# sensbaseGLCD.net
KiCad netlist of a schematic drawn in EAGLE
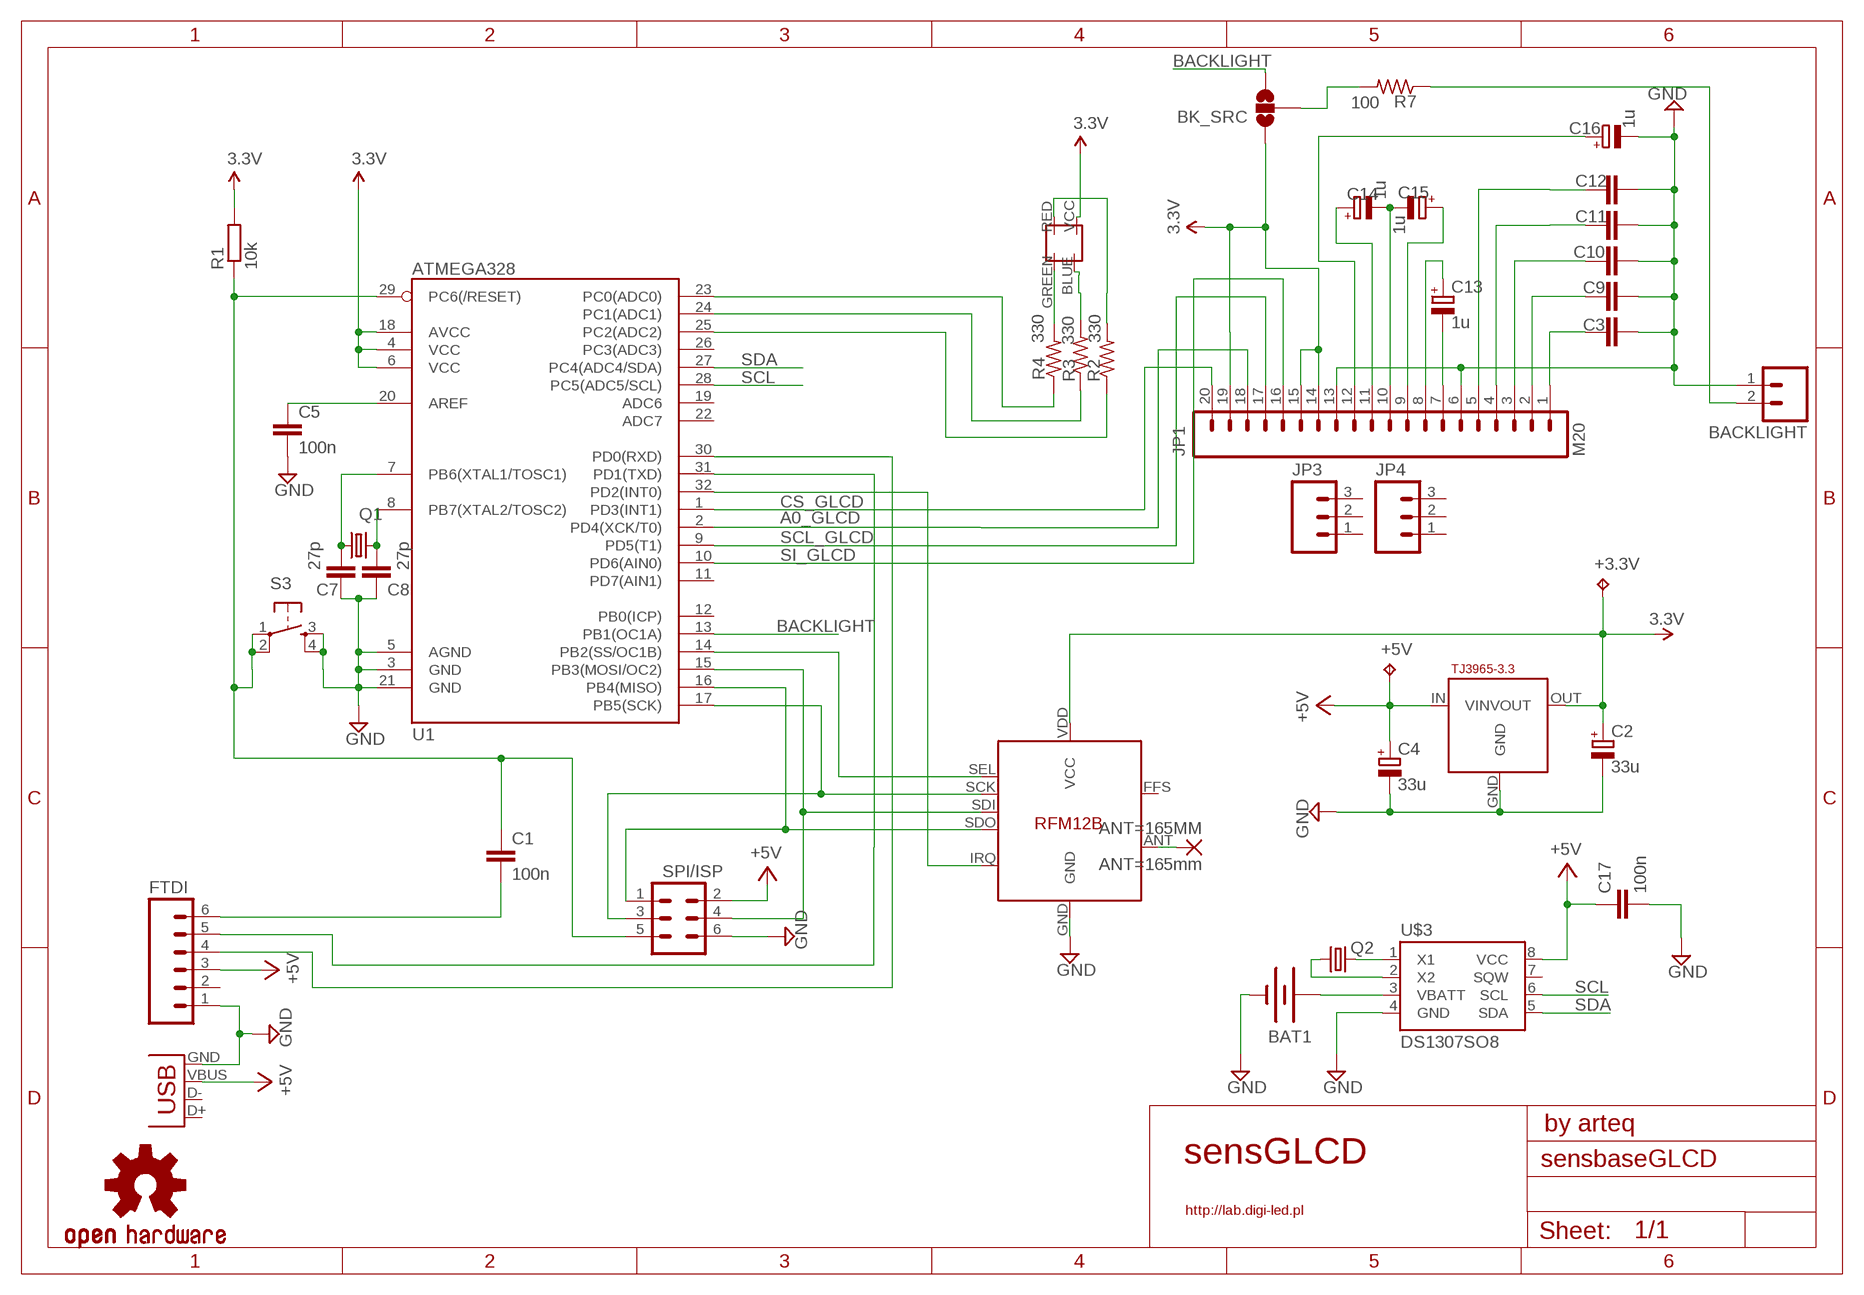
[diagram p0: schematic, sheet 1]

(export (version "E")
  (design (tool "Eeschema 10.0.6"))
  (components
    (comp (ref "+3.3V")
      (value "TPB1,27")
      (footprint "eagle-import:B1,27")
      (libsource (lib "eagle-import") (part "TPB1,27"))
    )
    (comp (ref "+5V")
      (value "TPB1,27")
      (footprint "eagle-import:B1,27")
      (libsource (lib "eagle-import") (part "TPB1,27"))
    )
    (comp (ref "3.3")
      (value "TJ3965-3.3")
      (footprint "eagle-import:SOT223")
      (libsource (lib "eagle-import") (part "TJ3965-3.3"))
    )
    (comp (ref "ANT=165MM")
      (value "ANT=165mm")
      (footprint "eagle-import:2,15_1,0")
      (libsource (lib "eagle-import") (part "2,15/1,0"))
    )
    (comp (ref "BACKLIGHT")
      (value "M02PTH")
      (footprint "eagle-import:1X02")
      (libsource (lib "eagle-import") (part "M02PTH"))
    )
    (comp (ref "BAT1")
      (value "BATTERY20PTH")
      (footprint "eagle-import:BATTCOM_20MM_PTH")
      (libsource (lib "eagle-import") (part "BATTERY20PTH"))
    )
    (comp (ref "BK_SRC")
      (value "SOLDERJUMPER_2WAYT")
      (footprint "eagle-import:SJ_2")
      (libsource (lib "eagle-import") (part "SOLDERJUMPER_2WAYT"))
    )
    (comp (ref "C1")
      (value "100n")
      (footprint "eagle-import:C0805")
      (libsource (lib "eagle-import") (part "C-EUC0805"))
    )
    (comp (ref "C2")
      (value "33u")
      (footprint "eagle-import:SMC_B")
      (libsource (lib "eagle-import") (part "CPOL-EUSMCB"))
    )
    (comp (ref "C3")
      (value "1u")
      (footprint "eagle-import:C0805")
      (libsource (lib "eagle-import") (part "C-EUC0805"))
    )
    (comp (ref "C4")
      (value "33u")
      (footprint "eagle-import:SMC_B")
      (libsource (lib "eagle-import") (part "CPOL-EUSMCB"))
    )
    (comp (ref "C5")
      (value "100n")
      (footprint "eagle-import:C0805")
      (libsource (lib "eagle-import") (part "C-EUC0805"))
    )
    (comp (ref "C7")
      (value "27p")
      (footprint "eagle-import:C0805")
      (libsource (lib "eagle-import") (part "C-EUC0805"))
    )
    (comp (ref "C8")
      (value "27p")
      (footprint "eagle-import:C0805")
      (libsource (lib "eagle-import") (part "C-EUC0805"))
    )
    (comp (ref "C9")
      (value "1u")
      (footprint "eagle-import:C0805")
      (libsource (lib "eagle-import") (part "C-EUC0805"))
    )
    (comp (ref "C10")
      (value "1u")
      (footprint "eagle-import:C0805")
      (libsource (lib "eagle-import") (part "C-EUC0805"))
    )
    (comp (ref "C11")
      (value "1u")
      (footprint "eagle-import:C0805")
      (libsource (lib "eagle-import") (part "C-EUC0805"))
    )
    (comp (ref "C12")
      (value "1u")
      (footprint "eagle-import:C0805")
      (libsource (lib "eagle-import") (part "C-EUC0805"))
    )
    (comp (ref "C13")
      (value "1u")
      (footprint "eagle-import:A_3216-18R")
      (libsource (lib "eagle-import") (part "CPOL-EUA/3216-18R"))
    )
    (comp (ref "C14")
      (value "1u")
      (footprint "eagle-import:A_3216-18R")
      (libsource (lib "eagle-import") (part "CPOL-EUA/3216-18R"))
    )
    (comp (ref "C15")
      (value "1u")
      (footprint "eagle-import:A_3216-18R")
      (libsource (lib "eagle-import") (part "CPOL-EUA/3216-18R"))
    )
    (comp (ref "C16")
      (value "1u")
      (footprint "eagle-import:A_3216-18R")
      (libsource (lib "eagle-import") (part "CPOL-EUA/3216-18R"))
    )
    (comp (ref "C17")
      (value "100n")
      (footprint "eagle-import:C0805")
      (libsource (lib "eagle-import") (part "C-EUC0805"))
    )
    (comp (ref "FTDI")
      (value "M06SIP")
      (footprint "eagle-import:1X06")
      (libsource (lib "eagle-import") (part "M06SIP"))
    )
    (comp (ref "JP1")
      (value "M20")
      (footprint "eagle-import:1X20")
      (libsource (lib "eagle-import") (part "M20"))
    )
    (comp (ref "JP3")
      (value "M03PTH")
      (footprint "eagle-import:1X03")
      (libsource (lib "eagle-import") (part "M03PTH"))
    )
    (comp (ref "JP4")
      (value "M03PTH")
      (footprint "eagle-import:1X03")
      (libsource (lib "eagle-import") (part "M03PTH"))
    )
    (comp (ref "Q1")
      (value "CRYSTALHC49UP")
      (footprint "eagle-import:HC49UP")
      (libsource (lib "eagle-import") (part "CRYSTALHC49UP"))
    )
    (comp (ref "Q2")
      (value "CRYSTALTC26H")
      (footprint "eagle-import:TC26H")
      (libsource (lib "eagle-import") (part "CRYSTALTC26H"))
    )
    (comp (ref "R1")
      (value "10k")
      (footprint "eagle-import:R0805")
      (libsource (lib "eagle-import") (part "R-EU_R0805"))
    )
    (comp (ref "R2")
      (value "330")
      (footprint "eagle-import:R0805")
      (libsource (lib "eagle-import") (part "R-US_R0805"))
    )
    (comp (ref "R3")
      (value "330")
      (footprint "eagle-import:R0805")
      (libsource (lib "eagle-import") (part "R-US_R0805"))
    )
    (comp (ref "R4")
      (value "330")
      (footprint "eagle-import:R0805")
      (libsource (lib "eagle-import") (part "R-US_R0805"))
    )
    (comp (ref "R7")
      (value "100")
      (footprint "eagle-import:R0805")
      (libsource (lib "eagle-import") (part "R-US_R0805"))
    )
    (comp (ref "RF433")
      (value "RFM12B")
      (footprint "eagle-import:RFM12B")
      (libsource (lib "eagle-import") (part "RFM12B"))
    )
    (comp (ref "S3")
      (value "TAC_SWITCHSMD")
      (footprint "eagle-import:TACTILE_SWITCH_SMD")
      (libsource (lib "eagle-import") (part "TAC_SWITCHSMD"))
    )
    (comp (ref "SV7")
      (value "SPI/ISP")
      (footprint "eagle-import:MA03-2")
      (libsource (lib "eagle-import") (part "MA03-2"))
    )
    (comp (ref "U$2")
      (value "OSHW-LOGOL")
      (footprint "eagle-import:OSHW-LOGO-L")
      (libsource (lib "eagle-import") (part "OSHW-LOGOL"))
    )
    (comp (ref "U$3")
      (value "DS1307SO8")
      (footprint "eagle-import:SO08")
      (libsource (lib "eagle-import") (part "DS1307SO8"))
    )
    (comp (ref "U$4")
      (value "RGB1206")
      (footprint "eagle-import:RGB1206")
      (libsource (lib "eagle-import") (part "RGB1206"))
    )
    (comp (ref "U1")
      (value "ATMEGA328")
      (footprint "eagle-import:TQFP32-08")
      (libsource (lib "eagle-import") (part "ATMEGA168"))
    )
    (comp (ref "X1")
      (value "USBSMD")
      (footprint "eagle-import:USB-MINIB")
      (libsource (lib "eagle-import") (part "USBSMD"))
    )
  )
  (nets
    (net (code "1") (name "+5V") (class "Default")
      (node (ref "+5V") (pin "TP") (pinfunction "TP_TP") (pintype "input"))
      (node (ref "3.3") (pin "IN") (pinfunction "VIN_IN") (pintype "input"))
      (node (ref "C17") (pin "1") (pinfunction "1_1") (pintype "passive"))
      (node (ref "C4") (pin "+") (pinfunction "+_+") (pintype "passive"))
      (node (ref "FTDI") (pin "3") (pinfunction "3_3") (pintype "passive"))
      (node (ref "SV7") (pin "2") (pinfunction "2_2") (pintype "passive"))
      (node (ref "U$3") (pin "8") (pinfunction "VCC_8") (pintype "bidirectional"))
      (node (ref "X1") (pin "VBUS") (pinfunction "VBUS_VBUS") (pintype "bidirectional"))
    )
    (net (code "2") (name "/A0_GLCD") (class "Default")
      (node (ref "JP1") (pin "18") (pinfunction "18_18") (pintype "passive"))
      (node (ref "U1") (pin "2") (pinfunction "PD4(XCK/T0)_2") (pintype "bidirectional"))
    )
    (net (code "3") (name "/BACKLIGHT") (class "Default")
      (node (ref "BK_SRC") (pin "3") (pinfunction "3_3") (pintype "passive"))
      (node (ref "U1") (pin "13") (pinfunction "PB1(OC1A)_13") (pintype "bidirectional"))
    )
    (net (code "4") (name "/CS_GLCD") (class "Default")
      (node (ref "JP1") (pin "20") (pinfunction "20_20") (pintype "passive"))
      (node (ref "U1") (pin "1") (pinfunction "PD3(INT1)_1") (pintype "bidirectional"))
    )
    (net (code "5") (name "/SCL") (class "Default")
      (node (ref "U$3") (pin "6") (pinfunction "SCL_6") (pintype "bidirectional"))
      (node (ref "U1") (pin "28") (pinfunction "PC5(ADC5/SCL)_28") (pintype "bidirectional"))
    )
    (net (code "6") (name "/SCL_GLCD") (class "Default")
      (node (ref "JP1") (pin "17") (pinfunction "17_17") (pintype "passive"))
      (node (ref "U1") (pin "9") (pinfunction "PD5(T1)_9") (pintype "bidirectional"))
    )
    (net (code "7") (name "/SDA") (class "Default")
      (node (ref "U$3") (pin "5") (pinfunction "SDA_5") (pintype "bidirectional"))
      (node (ref "U1") (pin "27") (pinfunction "PC4(ADC4/SDA)_27") (pintype "bidirectional"))
    )
    (net (code "8") (name "/SI_GLCD") (class "Default")
      (node (ref "JP1") (pin "16") (pinfunction "16_16") (pintype "passive"))
      (node (ref "U1") (pin "10") (pinfunction "PD6(AIN0)_10") (pintype "bidirectional"))
    )
    (net (code "9") (name "3.3V") (class "Default")
      (node (ref "+3.3V") (pin "TP") (pinfunction "TP_TP") (pintype "input"))
      (node (ref "3.3") (pin "OUT") (pinfunction "VOUT_OUT") (pintype "output"))
      (node (ref "BK_SRC") (pin "1") (pinfunction "1_1") (pintype "passive"))
      (node (ref "C2") (pin "+") (pinfunction "+_+") (pintype "passive"))
      (node (ref "JP1") (pin "14") (pinfunction "14_14") (pintype "passive"))
      (node (ref "JP1") (pin "15") (pinfunction "15_15") (pintype "passive"))
      (node (ref "JP1") (pin "19") (pinfunction "19_19") (pintype "passive"))
      (node (ref "R1") (pin "2") (pinfunction "2_2") (pintype "passive"))
      (node (ref "RF433") (pin "VDD") (pinfunction "VCC_VDD") (pintype "power_in"))
      (node (ref "U$4") (pin "VCC") (pinfunction "VCC_VCC") (pintype "bidirectional"))
      (node (ref "U1") (pin "18") (pinfunction "AVCC_18") (pintype "bidirectional"))
      (node (ref "U1") (pin "4") (pinfunction "VCC_4") (pintype "bidirectional"))
      (node (ref "U1") (pin "6") (pinfunction "VCC_6") (pintype "bidirectional"))
    )
    (net (code "10") (name "GND") (class "Default")
      (node (ref "3.3") (pin "GND") (pinfunction "GND_GND") (pintype "power_in"))
      (node (ref "BACKLIGHT") (pin "1") (pinfunction "1_1") (pintype "passive"))
      (node (ref "BAT1") (pin "2") (pinfunction "-_2") (pintype "power_in"))
      (node (ref "C10") (pin "2") (pinfunction "2_2") (pintype "passive"))
      (node (ref "C11") (pin "2") (pinfunction "2_2") (pintype "passive"))
      (node (ref "C12") (pin "2") (pinfunction "2_2") (pintype "passive"))
      (node (ref "C16") (pin "-") (pinfunction "-_-") (pintype "passive"))
      (node (ref "C17") (pin "2") (pinfunction "2_2") (pintype "passive"))
      (node (ref "C2") (pin "-") (pinfunction "-_-") (pintype "passive"))
      (node (ref "C3") (pin "2") (pinfunction "2_2") (pintype "passive"))
      (node (ref "C4") (pin "-") (pinfunction "-_-") (pintype "passive"))
      (node (ref "C5") (pin "2") (pinfunction "2_2") (pintype "passive"))
      (node (ref "C7") (pin "2") (pinfunction "2_2") (pintype "passive"))
      (node (ref "C8") (pin "2") (pinfunction "2_2") (pintype "passive"))
      (node (ref "C9") (pin "2") (pinfunction "2_2") (pintype "passive"))
      (node (ref "FTDI") (pin "1") (pinfunction "1_1") (pintype "passive"))
      (node (ref "JP1") (pin "13") (pinfunction "13_13") (pintype "passive"))
      (node (ref "JP1") (pin "6") (pinfunction "6_6") (pintype "passive"))
      (node (ref "RF433") (pin "GND") (pinfunction "GND_GND") (pintype "power_in"))
      (node (ref "S3") (pin "3") (pinfunction "3_3") (pintype "passive"))
      (node (ref "S3") (pin "4") (pinfunction "4_4") (pintype "passive"))
      (node (ref "SV7") (pin "6") (pinfunction "6_6") (pintype "passive"))
      (node (ref "U$3") (pin "4") (pinfunction "GND_4") (pintype "bidirectional"))
      (node (ref "U1") (pin "21") (pinfunction "GND_21") (pintype "bidirectional"))
      (node (ref "U1") (pin "3") (pinfunction "GND_3") (pintype "bidirectional"))
      (node (ref "U1") (pin "5") (pinfunction "AGND_5") (pintype "bidirectional"))
      (node (ref "X1") (pin "GND") (pinfunction "GND_GND") (pintype "bidirectional"))
    )
    (net (code "11") (name "Net-(ANT=165MM-P)") (class "Default")
      (node (ref "ANT=165MM") (pin "1") (pinfunction "P_1") (pintype "passive"))
      (node (ref "RF433") (pin "ANT") (pinfunction "ANT_ANT") (pintype "passive"))
    )
    (net (code "12") (name "Net-(BACKLIGHT-Pad2)") (class "Default")
      (node (ref "BACKLIGHT") (pin "2") (pinfunction "2_2") (pintype "passive"))
      (node (ref "R7") (pin "1") (pinfunction "1_1") (pintype "passive"))
    )
    (net (code "13") (name "Net-(BAT1-+)") (class "Default")
      (node (ref "BAT1") (pin "1") (pinfunction "+_1") (pintype "power_in"))
      (node (ref "U$3") (pin "3") (pinfunction "VBATT_3") (pintype "bidirectional"))
    )
    (net (code "14") (name "Net-(BK_SRC-Pad2)") (class "Default")
      (node (ref "BK_SRC") (pin "2") (pinfunction "2_2") (pintype "passive"))
      (node (ref "R7") (pin "2") (pinfunction "2_2") (pintype "passive"))
    )
    (net (code "15") (name "Net-(C1-Pad2)") (class "Default")
      (node (ref "C1") (pin "2") (pinfunction "2_2") (pintype "passive"))
      (node (ref "FTDI") (pin "6") (pinfunction "6_6") (pintype "passive"))
    )
    (net (code "16") (name "Net-(C3-Pad1)") (class "Default")
      (node (ref "C3") (pin "1") (pinfunction "1_1") (pintype "passive"))
      (node (ref "JP1") (pin "1") (pinfunction "1_1") (pintype "passive"))
    )
    (net (code "17") (name "Net-(C9-Pad1)") (class "Default")
      (node (ref "C9") (pin "1") (pinfunction "1_1") (pintype "passive"))
      (node (ref "JP1") (pin "2") (pinfunction "2_2") (pintype "passive"))
    )
    (net (code "18") (name "Net-(C10-Pad1)") (class "Default")
      (node (ref "C10") (pin "1") (pinfunction "1_1") (pintype "passive"))
      (node (ref "JP1") (pin "3") (pinfunction "3_3") (pintype "passive"))
    )
    (net (code "19") (name "Net-(C11-Pad1)") (class "Default")
      (node (ref "C11") (pin "1") (pinfunction "1_1") (pintype "passive"))
      (node (ref "JP1") (pin "4") (pinfunction "4_4") (pintype "passive"))
    )
    (net (code "20") (name "Net-(C12-Pad1)") (class "Default")
      (node (ref "C12") (pin "1") (pinfunction "1_1") (pintype "passive"))
      (node (ref "JP1") (pin "5") (pinfunction "5_5") (pintype "passive"))
    )
    (net (code "21") (name "Net-(C13-Pad+)") (class "Default")
      (node (ref "C13") (pin "+") (pinfunction "+_+") (pintype "passive"))
      (node (ref "JP1") (pin "8") (pinfunction "8_8") (pintype "passive"))
    )
    (net (code "22") (name "Net-(C13-Pad-)") (class "Default")
      (node (ref "C13") (pin "-") (pinfunction "-_-") (pintype "passive"))
      (node (ref "JP1") (pin "7") (pinfunction "7_7") (pintype "passive"))
    )
    (net (code "23") (name "Net-(C14-Pad+)") (class "Default")
      (node (ref "C14") (pin "+") (pinfunction "+_+") (pintype "passive"))
      (node (ref "JP1") (pin "11") (pinfunction "11_11") (pintype "passive"))
    )
    (net (code "24") (name "Net-(C14-Pad-)") (class "Default")
      (node (ref "C14") (pin "-") (pinfunction "-_-") (pintype "passive"))
      (node (ref "C15") (pin "-") (pinfunction "-_-") (pintype "passive"))
      (node (ref "JP1") (pin "10") (pinfunction "10_10") (pintype "passive"))
    )
    (net (code "25") (name "Net-(C15-Pad+)") (class "Default")
      (node (ref "C15") (pin "+") (pinfunction "+_+") (pintype "passive"))
      (node (ref "JP1") (pin "9") (pinfunction "9_9") (pintype "passive"))
    )
    (net (code "26") (name "Net-(C16-Pad+)") (class "Default")
      (node (ref "C16") (pin "+") (pinfunction "+_+") (pintype "passive"))
      (node (ref "JP1") (pin "12") (pinfunction "12_12") (pintype "passive"))
    )
    (net (code "27") (name "Net-(U$3-X1)") (class "Default")
      (node (ref "Q2") (pin "1") (pinfunction "1_1") (pintype "passive"))
      (node (ref "U$3") (pin "1") (pinfunction "X1_1") (pintype "bidirectional"))
    )
    (net (code "28") (name "Net-(U$3-X2)") (class "Default")
      (node (ref "Q2") (pin "2") (pinfunction "2_2") (pintype "passive"))
      (node (ref "U$3") (pin "2") (pinfunction "X2_2") (pintype "bidirectional"))
    )
    (net (code "29") (name "Net-(U$4-BL)") (class "Default")
      (node (ref "R3") (pin "2") (pinfunction "2_2") (pintype "passive"))
      (node (ref "U$4") (pin "BLUE") (pinfunction "BL_BLUE") (pintype "bidirectional"))
    )
    (net (code "30") (name "Net-(U$4-GR)") (class "Default")
      (node (ref "R4") (pin "2") (pinfunction "2_2") (pintype "passive"))
      (node (ref "U$4") (pin "GREEN") (pinfunction "GR_GREEN") (pintype "bidirectional"))
    )
    (net (code "31") (name "Net-(U$4-RE)") (class "Default")
      (node (ref "R2") (pin "2") (pinfunction "2_2") (pintype "passive"))
      (node (ref "U$4") (pin "RED") (pinfunction "RE_RED") (pintype "bidirectional"))
    )
    (net (code "32") (name "Net-(U1-AREF)") (class "Default")
      (node (ref "C5") (pin "1") (pinfunction "1_1") (pintype "passive"))
      (node (ref "U1") (pin "20") (pinfunction "AREF_20") (pintype "bidirectional"))
    )
    (net (code "33") (name "Net-(U1-PB2(SS{slash}OC1B))") (class "Default")
      (node (ref "RF433") (pin "SEL") (pinfunction "SEL_SEL") (pintype "input"))
      (node (ref "U1") (pin "14") (pinfunction "PB2(SS/OC1B)_14") (pintype "bidirectional"))
    )
    (net (code "34") (name "Net-(U1-PB3(MOSI{slash}OC2))") (class "Default")
      (node (ref "RF433") (pin "SDI") (pinfunction "SDI_SDI") (pintype "input"))
      (node (ref "SV7") (pin "4") (pinfunction "4_4") (pintype "passive"))
      (node (ref "U1") (pin "15") (pinfunction "PB3(MOSI/OC2)_15") (pintype "bidirectional"))
    )
    (net (code "35") (name "Net-(U1-PB4(MISO))") (class "Default")
      (node (ref "RF433") (pin "SDO") (pinfunction "SDO_SDO") (pintype "output"))
      (node (ref "SV7") (pin "1") (pinfunction "1_1") (pintype "passive"))
      (node (ref "U1") (pin "16") (pinfunction "PB4(MISO)_16") (pintype "bidirectional"))
    )
    (net (code "36") (name "Net-(U1-PB5(SCK))") (class "Default")
      (node (ref "RF433") (pin "SCK") (pinfunction "SCK_SCK") (pintype "input"))
      (node (ref "SV7") (pin "3") (pinfunction "3_3") (pintype "passive"))
      (node (ref "U1") (pin "17") (pinfunction "PB5(SCK)_17") (pintype "bidirectional"))
    )
    (net (code "37") (name "Net-(U1-PB6(XTAL1{slash}TOSC1))") (class "Default")
      (node (ref "C7") (pin "1") (pinfunction "1_1") (pintype "passive"))
      (node (ref "Q1") (pin "1") (pinfunction "1_1") (pintype "passive"))
      (node (ref "U1") (pin "7") (pinfunction "PB6(XTAL1/TOSC1)_7") (pintype "bidirectional"))
    )
    (net (code "38") (name "Net-(U1-PB7(XTAL2{slash}TOSC2))") (class "Default")
      (node (ref "C8") (pin "1") (pinfunction "1_1") (pintype "passive"))
      (node (ref "Q1") (pin "2") (pinfunction "2_2") (pintype "passive"))
      (node (ref "U1") (pin "8") (pinfunction "PB7(XTAL2/TOSC2)_8") (pintype "bidirectional"))
    )
    (net (code "39") (name "Net-(U1-PC0(ADC0))") (class "Default")
      (node (ref "R4") (pin "1") (pinfunction "1_1") (pintype "passive"))
      (node (ref "U1") (pin "23") (pinfunction "PC0(ADC0)_23") (pintype "bidirectional"))
    )
    (net (code "40") (name "Net-(U1-PC1(ADC1))") (class "Default")
      (node (ref "R3") (pin "1") (pinfunction "1_1") (pintype "passive"))
      (node (ref "U1") (pin "24") (pinfunction "PC1(ADC1)_24") (pintype "bidirectional"))
    )
    (net (code "41") (name "Net-(U1-PC2(ADC2))") (class "Default")
      (node (ref "R2") (pin "1") (pinfunction "1_1") (pintype "passive"))
      (node (ref "U1") (pin "25") (pinfunction "PC2(ADC2)_25") (pintype "bidirectional"))
    )
    (net (code "42") (name "Net-(U1-PC6({slash}RESET))") (class "Default")
      (node (ref "C1") (pin "1") (pinfunction "1_1") (pintype "passive"))
      (node (ref "R1") (pin "1") (pinfunction "1_1") (pintype "passive"))
      (node (ref "S3") (pin "1") (pinfunction "1_1") (pintype "passive"))
      (node (ref "S3") (pin "2") (pinfunction "2_2") (pintype "passive"))
      (node (ref "SV7") (pin "5") (pinfunction "5_5") (pintype "passive"))
      (node (ref "U1") (pin "29") (pinfunction "PC6(/RESET)_29") (pintype "bidirectional"))
    )
    (net (code "43") (name "Net-(U1-PD0(RXD))") (class "Default")
      (node (ref "FTDI") (pin "4") (pinfunction "4_4") (pintype "passive"))
      (node (ref "U1") (pin "30") (pinfunction "PD0(RXD)_30") (pintype "bidirectional"))
    )
    (net (code "44") (name "Net-(U1-PD1(TXD))") (class "Default")
      (node (ref "FTDI") (pin "5") (pinfunction "5_5") (pintype "passive"))
      (node (ref "U1") (pin "31") (pinfunction "PD1(TXD)_31") (pintype "bidirectional"))
    )
    (net (code "45") (name "Net-(U1-PD2(INT0))") (class "Default")
      (node (ref "RF433") (pin "IRQ") (pinfunction "IRQ_IRQ") (pintype "open_collector"))
      (node (ref "U1") (pin "32") (pinfunction "PD2(INT0)_32") (pintype "bidirectional"))
    )
    (net (code "46") (name "unconnected-(FTDI-Pad2)") (class "Default")
      (node (ref "FTDI") (pin "2") (pinfunction "2_2") (pintype "passive"))
    )
    (net (code "47") (name "unconnected-(JP3-Pad1)") (class "Default")
      (node (ref "JP3") (pin "1") (pinfunction "1_1") (pintype "passive"))
    )
    (net (code "48") (name "unconnected-(JP3-Pad2)") (class "Default")
      (node (ref "JP3") (pin "2") (pinfunction "2_2") (pintype "passive"))
    )
    (net (code "49") (name "unconnected-(JP3-Pad3)") (class "Default")
      (node (ref "JP3") (pin "3") (pinfunction "3_3") (pintype "passive"))
    )
    (net (code "50") (name "unconnected-(JP4-Pad1)") (class "Default")
      (node (ref "JP4") (pin "1") (pinfunction "1_1") (pintype "passive"))
    )
    (net (code "51") (name "unconnected-(JP4-Pad2)") (class "Default")
      (node (ref "JP4") (pin "2") (pinfunction "2_2") (pintype "passive"))
    )
    (net (code "52") (name "unconnected-(JP4-Pad3)") (class "Default")
      (node (ref "JP4") (pin "3") (pinfunction "3_3") (pintype "passive"))
    )
    (net (code "53") (name "unconnected-(RF433-PadFFS)") (class "Default")
      (node (ref "RF433") (pin "FFS") (pinfunction "FFS_FFS") (pintype "bidirectional"))
    )
    (net (code "54") (name "unconnected-(U$3-SQW-Pad7)") (class "Default")
      (node (ref "U$3") (pin "7") (pinfunction "SQW_7") (pintype "bidirectional"))
    )
    (net (code "55") (name "unconnected-(U1-ADC6-Pad19)") (class "Default")
      (node (ref "U1") (pin "19") (pinfunction "ADC6_19") (pintype "bidirectional"))
    )
    (net (code "56") (name "unconnected-(U1-ADC7-Pad22)") (class "Default")
      (node (ref "U1") (pin "22") (pinfunction "ADC7_22") (pintype "bidirectional"))
    )
    (net (code "57") (name "unconnected-(U1-PB0(ICP)-Pad12)") (class "Default")
      (node (ref "U1") (pin "12") (pinfunction "PB0(ICP)_12") (pintype "bidirectional"))
    )
    (net (code "58") (name "unconnected-(U1-PC3(ADC3)-Pad26)") (class "Default")
      (node (ref "U1") (pin "26") (pinfunction "PC3(ADC3)_26") (pintype "bidirectional"))
    )
    (net (code "59") (name "unconnected-(U1-PD7(AIN1)-Pad11)") (class "Default")
      (node (ref "U1") (pin "11") (pinfunction "PD7(AIN1)_11") (pintype "bidirectional"))
    )
    (net (code "60") (name "unconnected-(X1-PadD+)") (class "Default")
      (node (ref "X1") (pin "D+") (pinfunction "D+_D+") (pintype "bidirectional"))
    )
    (net (code "61") (name "unconnected-(X1-PadD-)") (class "Default")
      (node (ref "X1") (pin "D-") (pinfunction "D-_D-") (pintype "bidirectional"))
    )
  )
)
